# V2_7_7.net
KiCad netlist of a schematic drawn in EAGLE
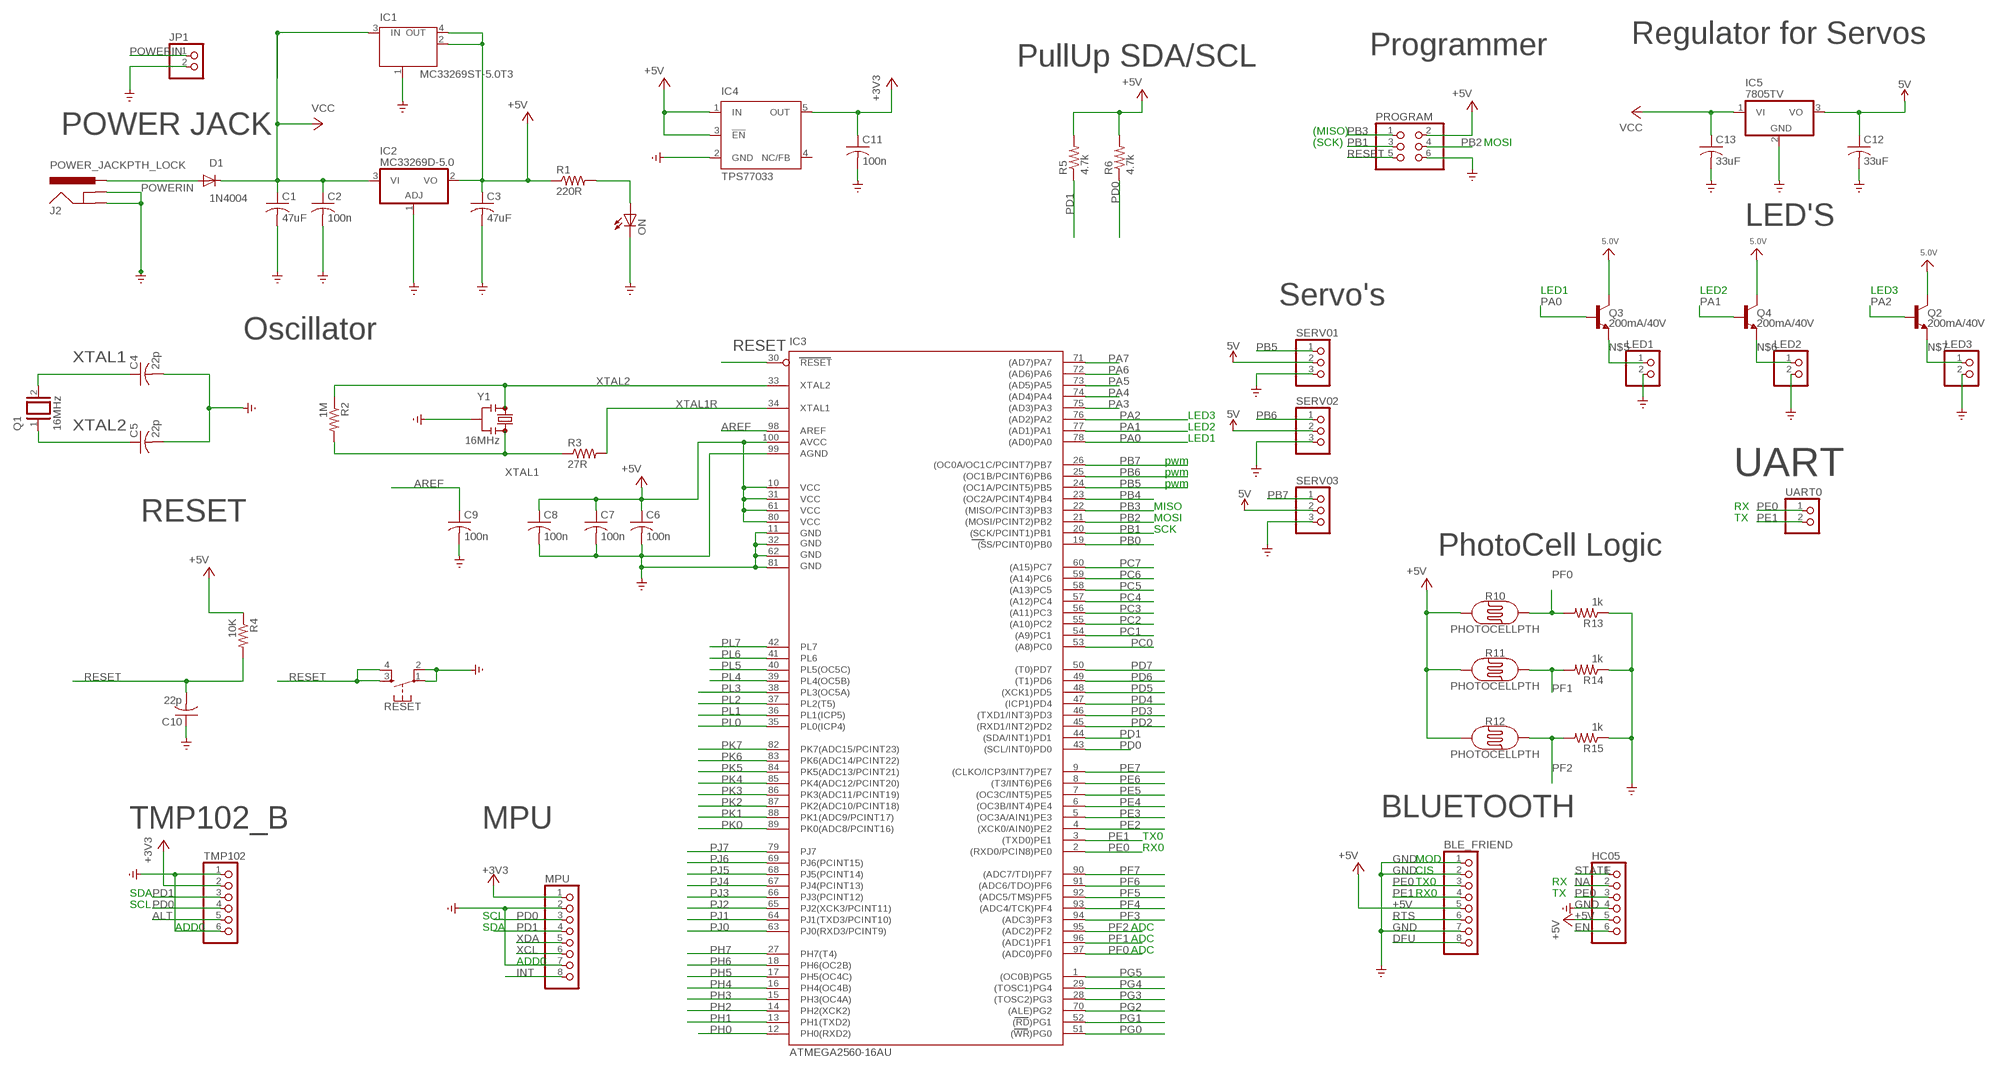
[diagram p0: schematic, sheet 1, part 1 of 2]
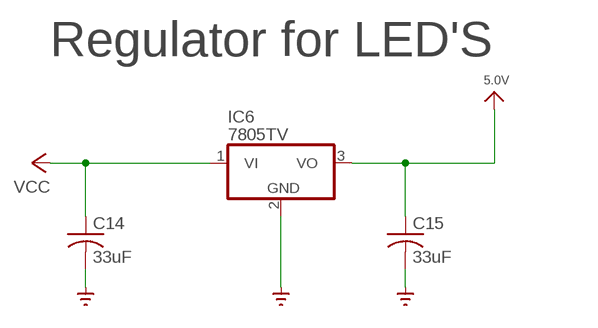
[diagram p1: schematic, sheet 1, part 2 of 2]

(export (version "E")
  (design (tool "Eeschema 10.0.6"))
  (components
    (comp (ref "BLE_FRIEND")
      (value "PINHD-1X8")
      (footprint "eagle-import:1X08")
      (libsource (lib "eagle-import") (part "PINHD-1X8"))
    )
    (comp (ref "C1")
      (value "47uF")
      (footprint "eagle-import:C025-024X044")
      (libsource (lib "eagle-import") (part "C-US025-024X044"))
    )
    (comp (ref "C2")
      (value "100n")
      (footprint "eagle-import:C025-024X044")
      (libsource (lib "eagle-import") (part "C-US025-024X044"))
    )
    (comp (ref "C3")
      (value "47uF")
      (footprint "eagle-import:C025-024X044")
      (libsource (lib "eagle-import") (part "C-US025-024X044"))
    )
    (comp (ref "C4")
      (value "22p")
      (footprint "eagle-import:C025-024X044")
      (libsource (lib "eagle-import") (part "C-US025-024X044"))
    )
    (comp (ref "C5")
      (value "22p")
      (footprint "eagle-import:C025-024X044")
      (libsource (lib "eagle-import") (part "C-US025-024X044"))
    )
    (comp (ref "C6")
      (value "100n")
      (footprint "eagle-import:C025-024X044")
      (libsource (lib "eagle-import") (part "C-US025-024X044"))
    )
    (comp (ref "C7")
      (value "100n")
      (footprint "eagle-import:C025-024X044")
      (libsource (lib "eagle-import") (part "C-US025-024X044"))
    )
    (comp (ref "C8")
      (value "100n")
      (footprint "eagle-import:C025-024X044")
      (libsource (lib "eagle-import") (part "C-US025-024X044"))
    )
    (comp (ref "C9")
      (value "100n")
      (footprint "eagle-import:C025-024X044")
      (libsource (lib "eagle-import") (part "C-US025-024X044"))
    )
    (comp (ref "C10")
      (value "22p")
      (footprint "eagle-import:C025-024X044")
      (libsource (lib "eagle-import") (part "C-US025-024X044"))
    )
    (comp (ref "C11")
      (value "100n")
      (footprint "eagle-import:C025-024X044")
      (libsource (lib "eagle-import") (part "C-US025-024X044"))
    )
    (comp (ref "C12")
      (value "33uF")
      (footprint "eagle-import:C025-024X044")
      (libsource (lib "eagle-import") (part "C-US025-024X044"))
    )
    (comp (ref "C13")
      (value "33uF")
      (footprint "eagle-import:C025-024X044")
      (libsource (lib "eagle-import") (part "C-US025-024X044"))
    )
    (comp (ref "C14")
      (value "33uF")
      (footprint "eagle-import:C025-024X044")
      (libsource (lib "eagle-import") (part "C-US025-024X044"))
    )
    (comp (ref "C15")
      (value "33uF")
      (footprint "eagle-import:C025-024X044")
      (libsource (lib "eagle-import") (part "C-US025-024X044"))
    )
    (comp (ref "D1")
      (value "1N4004")
      (footprint "eagle-import:DO41-10")
      (libsource (lib "eagle-import") (part "1N4004"))
    )
    (comp (ref "HC05")
      (value "PINHD-1X6")
      (footprint "eagle-import:1X06")
      (libsource (lib "eagle-import") (part "pinhead@1_PINHD-1X6"))
    )
    (comp (ref "IC1")
      (value "MC33269ST-5.0T3")
      (footprint "eagle-import:SOT223")
      (libsource (lib "eagle-import") (part "MC33269ST-3.3T3"))
    )
    (comp (ref "IC2")
      (value "MC33269D-5.0")
      (footprint "eagle-import:DPACK")
      (libsource (lib "eagle-import") (part "MC33269?D-5.0"))
    )
    (comp (ref "IC3")
      (value "ATMEGA2560-16AU")
      (footprint "eagle-import:TQFP100")
      (libsource (lib "eagle-import") (part "ATMEGAAU2560-16"))
    )
    (comp (ref "IC4")
      (value "TPS77033")
      (footprint "eagle-import:SOT23-DBV")
      (fields (field (name "MF") "TEXAS INSTRUMENTS") (field (name "MPN") "TPS77033DBVT"))
      (libsource (lib "eagle-import") (part "TPS77033"))
    )
    (comp (ref "IC5")
      (value "7805TV")
      (footprint "eagle-import:TO220V")
      (libsource (lib "eagle-import") (part "78TV05"))
    )
    (comp (ref "IC6")
      (value "7805TV")
      (footprint "eagle-import:TO220V")
      (libsource (lib "eagle-import") (part "78TV05"))
    )
    (comp (ref "J2")
      (value "POWER_JACKPTH_LOCK")
      (footprint "eagle-import:POWER_JACK_PTH_LOCK")
      (libsource (lib "eagle-import") (part "POWER_JACKPTH_LOCK"))
    )
    (comp (ref "JP1")
      (value "PINHD-1X2")
      (footprint "eagle-import:1X02")
      (libsource (lib "eagle-import") (part "pinhead@1_PINHD-1X2"))
    )
    (comp (ref "LED1")
      (value "PINHD-1X2")
      (footprint "eagle-import:1X02")
      (libsource (lib "eagle-import") (part "PINHD-1X2"))
    )
    (comp (ref "LED2")
      (value "PINHD-1X2")
      (footprint "eagle-import:1X02")
      (libsource (lib "eagle-import") (part "PINHD-1X2"))
    )
    (comp (ref "LED3")
      (value "PINHD-1X2")
      (footprint "eagle-import:1X02")
      (libsource (lib "eagle-import") (part "PINHD-1X2"))
    )
    (comp (ref "MPU")
      (value "PINHD-1X8")
      (footprint "eagle-import:1X08")
      (libsource (lib "eagle-import") (part "PINHD-1X8"))
    )
    (comp (ref "ON")
      (value "LED3MM")
      (footprint "eagle-import:LED3MM")
      (libsource (lib "eagle-import") (part "LED3MM"))
    )
    (comp (ref "PROGRAM")
      (value "PINHD-2X3")
      (footprint "eagle-import:2X03")
      (libsource (lib "eagle-import") (part "PINHD-2X3"))
    )
    (comp (ref "Q1")
      (value "16MHz")
      (footprint "eagle-import:QS")
      (libsource (lib "eagle-import") (part "XTAL/S"))
    )
    (comp (ref "Q2")
      (value "200mA/40V")
      (footprint "eagle-import:TO-92")
      (libsource (lib "eagle-import") (part "TRANS_NPN-2N3904"))
    )
    (comp (ref "Q3")
      (value "200mA/40V")
      (footprint "eagle-import:TO-92")
      (libsource (lib "eagle-import") (part "TRANS_NPN-2N3904"))
    )
    (comp (ref "Q4")
      (value "200mA/40V")
      (footprint "eagle-import:TO-92")
      (libsource (lib "eagle-import") (part "TRANS_NPN-2N3904"))
    )
    (comp (ref "R1")
      (value "220R")
      (footprint "eagle-import:0204V")
      (libsource (lib "eagle-import") (part "R-US_0204/2V"))
    )
    (comp (ref "R2")
      (value "1M")
      (footprint "eagle-import:0204V")
      (libsource (lib "eagle-import") (part "R-US_0204/2V"))
    )
    (comp (ref "R3")
      (value "27R")
      (footprint "eagle-import:0204V")
      (libsource (lib "eagle-import") (part "R-US_0204/2V"))
    )
    (comp (ref "R4")
      (value "10K")
      (footprint "eagle-import:0204V")
      (libsource (lib "eagle-import") (part "R-US_0204/2V"))
    )
    (comp (ref "R5")
      (value "4.7k")
      (footprint "eagle-import:0204V")
      (libsource (lib "eagle-import") (part "R-US_0204/2V"))
    )
    (comp (ref "R6")
      (value "4.7k")
      (footprint "eagle-import:0204V")
      (libsource (lib "eagle-import") (part "R-US_0204/2V"))
    )
    (comp (ref "R10")
      (value "PHOTOCELLPTH")
      (footprint "eagle-import:PHOTOCELL")
      (libsource (lib "eagle-import") (part "PHOTOCELLPTH"))
    )
    (comp (ref "R11")
      (value "PHOTOCELLPTH")
      (footprint "eagle-import:PHOTOCELL")
      (libsource (lib "eagle-import") (part "PHOTOCELLPTH"))
    )
    (comp (ref "R12")
      (value "PHOTOCELLPTH")
      (footprint "eagle-import:PHOTOCELL")
      (libsource (lib "eagle-import") (part "PHOTOCELLPTH"))
    )
    (comp (ref "R13")
      (value "1k")
      (footprint "eagle-import:0204V")
      (libsource (lib "eagle-import") (part "R-US_0204/2V"))
    )
    (comp (ref "R14")
      (value "1k")
      (footprint "eagle-import:0204V")
      (libsource (lib "eagle-import") (part "R-US_0204/2V"))
    )
    (comp (ref "R15")
      (value "1k")
      (footprint "eagle-import:0204V")
      (libsource (lib "eagle-import") (part "R-US_0204/2V"))
    )
    (comp (ref "RESET")
      (value "MOMENTARY-SWITCH-SPST-2-SMD-5.2MM")
      (footprint "eagle-import:TACTILE_SWITCH_SMD_5.2MM")
      (libsource (lib "eagle-import") (part "MOMENTARY-SWITCH-SPST-2-SMD-5.2MM"))
    )
    (comp (ref "SERV01")
      (value "PINHD-1X3")
      (footprint "eagle-import:1X03")
      (libsource (lib "eagle-import") (part "PINHD-1X3"))
    )
    (comp (ref "SERV02")
      (value "PINHD-1X3")
      (footprint "eagle-import:1X03")
      (libsource (lib "eagle-import") (part "PINHD-1X3"))
    )
    (comp (ref "SERV03")
      (value "PINHD-1X3")
      (footprint "eagle-import:1X03")
      (libsource (lib "eagle-import") (part "PINHD-1X3"))
    )
    (comp (ref "TMP102")
      (value "PINHD-1X6")
      (footprint "eagle-import:1X06")
      (libsource (lib "eagle-import") (part "PINHD-1X6"))
    )
    (comp (ref "UART0")
      (value "PINHD-1X2")
      (footprint "eagle-import:1X02")
      (libsource (lib "eagle-import") (part "PINHD-1X2"))
    )
    (comp (ref "Y1")
      (value "16MHz")
      (footprint "eagle-import:RESONATOR-SMD-3.2X1.3")
      (libsource (lib "eagle-import") (part "RESONATORSMD-3.2X1.3"))
    )
  )
  (nets
    (net (code "1") (name "+3V3") (class "Default")
      (node (ref "C11") (pin "1") (pinfunction "1_1") (pintype "passive"))
      (node (ref "IC4") (pin "5") (pinfunction "OUT_5") (pintype "passive"))
      (node (ref "MPU") (pin "1") (pinfunction "1_1") (pintype "passive"))
      (node (ref "TMP102") (pin "2") (pinfunction "2_2") (pintype "passive"))
    )
    (net (code "2") (name "+5V") (class "Default")
      (node (ref "BLE_FRIEND") (pin "5") (pinfunction "5_5") (pintype "passive"))
      (node (ref "C3") (pin "1") (pinfunction "1_1") (pintype "passive"))
      (node (ref "C6") (pin "1") (pinfunction "1_1") (pintype "passive"))
      (node (ref "C7") (pin "1") (pinfunction "1_1") (pintype "passive"))
      (node (ref "C8") (pin "1") (pinfunction "1_1") (pintype "passive"))
      (node (ref "HC05") (pin "5") (pinfunction "5_5") (pintype "passive"))
      (node (ref "IC1") (pin "2") (pinfunction "OUT_2") (pintype "passive"))
      (node (ref "IC1") (pin "4") (pinfunction "OUT_4") (pintype "passive"))
      (node (ref "IC2") (pin "2") (pinfunction "VO_2") (pintype "passive"))
      (node (ref "IC3") (pin "10") (pinfunction "VCC_10") (pintype "power_in"))
      (node (ref "IC3") (pin "100") (pinfunction "AVCC_100") (pintype "power_in"))
      (node (ref "IC3") (pin "31") (pinfunction "VCC1_31") (pintype "power_in"))
      (node (ref "IC3") (pin "61") (pinfunction "VCC2_61") (pintype "power_in"))
      (node (ref "IC3") (pin "80") (pinfunction "VCC3_80") (pintype "power_in"))
      (node (ref "IC4") (pin "1") (pinfunction "IN_1") (pintype "input"))
      (node (ref "IC4") (pin "3") (pinfunction "~{EN}_3") (pintype "input"))
      (node (ref "PROGRAM") (pin "2") (pinfunction "2_2") (pintype "passive"))
      (node (ref "R1") (pin "1") (pinfunction "1_1") (pintype "passive"))
      (node (ref "R10") (pin "1") (pinfunction "P$1_1") (pintype "bidirectional"))
      (node (ref "R11") (pin "1") (pinfunction "P$1_1") (pintype "bidirectional"))
      (node (ref "R12") (pin "1") (pinfunction "P$1_1") (pintype "bidirectional"))
      (node (ref "R4") (pin "1") (pinfunction "1_1") (pintype "passive"))
      (node (ref "R5") (pin "2") (pinfunction "2_2") (pintype "passive"))
      (node (ref "R6") (pin "2") (pinfunction "2_2") (pintype "passive"))
    )
    (net (code "3") (name "/ALT") (class "Default")
      (node (ref "TMP102") (pin "5") (pinfunction "5_5") (pintype "passive"))
    )
    (net (code "4") (name "/AREF") (class "Default")
      (node (ref "C9") (pin "1") (pinfunction "1_1") (pintype "passive"))
      (node (ref "IC3") (pin "98") (pinfunction "AREF_98") (pintype "bidirectional"))
    )
    (net (code "5") (name "/DFU") (class "Default")
      (node (ref "BLE_FRIEND") (pin "8") (pinfunction "8_8") (pintype "passive"))
    )
    (net (code "6") (name "/EN") (class "Default")
      (node (ref "HC05") (pin "6") (pinfunction "6_6") (pintype "passive"))
    )
    (net (code "7") (name "/INT") (class "Default")
      (node (ref "MPU") (pin "8") (pinfunction "8_8") (pintype "passive"))
    )
    (net (code "8") (name "/N$5") (class "Default")
      (node (ref "LED1") (pin "1") (pinfunction "1_1") (pintype "passive"))
      (node (ref "Q3") (pin "1") (pinfunction "E_1") (pintype "passive"))
    )
    (net (code "9") (name "/N$6") (class "Default")
      (node (ref "LED2") (pin "1") (pinfunction "1_1") (pintype "passive"))
      (node (ref "Q4") (pin "1") (pinfunction "E_1") (pintype "passive"))
    )
    (net (code "10") (name "/N$7") (class "Default")
      (node (ref "LED3") (pin "1") (pinfunction "1_1") (pintype "passive"))
      (node (ref "Q2") (pin "1") (pinfunction "E_1") (pintype "passive"))
    )
    (net (code "11") (name "/NA") (class "Default")
      (node (ref "HC05") (pin "2") (pinfunction "2_2") (pintype "passive"))
    )
    (net (code "12") (name "/PA0") (class "Default")
      (node (ref "IC3") (pin "78") (pinfunction "(AD0)PA0_78") (pintype "bidirectional"))
      (node (ref "Q3") (pin "2") (pinfunction "B_2") (pintype "passive"))
    )
    (net (code "13") (name "/PA1") (class "Default")
      (node (ref "IC3") (pin "77") (pinfunction "(AD1)PA1_77") (pintype "bidirectional"))
      (node (ref "Q4") (pin "2") (pinfunction "B_2") (pintype "passive"))
    )
    (net (code "14") (name "/PA2") (class "Default")
      (node (ref "IC3") (pin "76") (pinfunction "(AD2)PA2_76") (pintype "bidirectional"))
      (node (ref "Q2") (pin "2") (pinfunction "B_2") (pintype "passive"))
    )
    (net (code "15") (name "/PA3") (class "Default")
      (node (ref "IC3") (pin "75") (pinfunction "(AD3)PA3_75") (pintype "bidirectional"))
    )
    (net (code "16") (name "/PA4") (class "Default")
      (node (ref "IC3") (pin "74") (pinfunction "(AD4)PA4_74") (pintype "bidirectional"))
    )
    (net (code "17") (name "/PA5") (class "Default")
      (node (ref "IC3") (pin "73") (pinfunction "(AD5)PA5_73") (pintype "bidirectional"))
    )
    (net (code "18") (name "/PA6") (class "Default")
      (node (ref "IC3") (pin "72") (pinfunction "(AD6)PA6_72") (pintype "bidirectional"))
    )
    (net (code "19") (name "/PA7") (class "Default")
      (node (ref "IC3") (pin "71") (pinfunction "(AD7)PA7_71") (pintype "bidirectional"))
    )
    (net (code "20") (name "/PB0") (class "Default")
      (node (ref "IC3") (pin "19") (pinfunction "(SS/PCINT0)PB0_19") (pintype "bidirectional"))
    )
    (net (code "21") (name "/PB1") (class "Default")
      (node (ref "IC3") (pin "20") (pinfunction "(SCK/PCINT1)PB1_20") (pintype "bidirectional"))
      (node (ref "PROGRAM") (pin "3") (pinfunction "3_3") (pintype "passive"))
    )
    (net (code "22") (name "/PB2") (class "Default")
      (node (ref "IC3") (pin "21") (pinfunction "(MOSI/PCINT2)PB2_21") (pintype "bidirectional"))
      (node (ref "PROGRAM") (pin "4") (pinfunction "4_4") (pintype "passive"))
    )
    (net (code "23") (name "/PB3") (class "Default")
      (node (ref "IC3") (pin "22") (pinfunction "(MISO/PCINT3)PB3_22") (pintype "bidirectional"))
      (node (ref "PROGRAM") (pin "1") (pinfunction "1_1") (pintype "passive"))
    )
    (net (code "24") (name "/PB4") (class "Default")
      (node (ref "IC3") (pin "23") (pinfunction "(OC2A/PCINT4)PB4_23") (pintype "bidirectional"))
    )
    (net (code "25") (name "/PB5") (class "Default")
      (node (ref "IC3") (pin "24") (pinfunction "(OC1A/PCINT5)PB5_24") (pintype "bidirectional"))
      (node (ref "SERV01") (pin "1") (pinfunction "1_1") (pintype "passive"))
    )
    (net (code "26") (name "/PB6") (class "Default")
      (node (ref "IC3") (pin "25") (pinfunction "(OC1B/PCINT6)PB6_25") (pintype "bidirectional"))
      (node (ref "SERV02") (pin "1") (pinfunction "1_1") (pintype "passive"))
    )
    (net (code "27") (name "/PB7") (class "Default")
      (node (ref "IC3") (pin "26") (pinfunction "(OC0A/OC1C/PCINT7)PB7_26") (pintype "bidirectional"))
      (node (ref "SERV03") (pin "1") (pinfunction "1_1") (pintype "passive"))
    )
    (net (code "28") (name "/PC0") (class "Default")
      (node (ref "IC3") (pin "53") (pinfunction "(A8)PC0_53") (pintype "bidirectional"))
    )
    (net (code "29") (name "/PC1") (class "Default")
      (node (ref "IC3") (pin "54") (pinfunction "(A9)PC1_54") (pintype "bidirectional"))
    )
    (net (code "30") (name "/PC2") (class "Default")
      (node (ref "IC3") (pin "55") (pinfunction "(A10)PC2_55") (pintype "bidirectional"))
    )
    (net (code "31") (name "/PC3") (class "Default")
      (node (ref "IC3") (pin "56") (pinfunction "(A11)PC3_56") (pintype "bidirectional"))
    )
    (net (code "32") (name "/PC4") (class "Default")
      (node (ref "IC3") (pin "57") (pinfunction "(A12)PC4_57") (pintype "bidirectional"))
    )
    (net (code "33") (name "/PC5") (class "Default")
      (node (ref "IC3") (pin "58") (pinfunction "(A13)PC5_58") (pintype "bidirectional"))
    )
    (net (code "34") (name "/PC6") (class "Default")
      (node (ref "IC3") (pin "59") (pinfunction "(A14)PC6_59") (pintype "bidirectional"))
    )
    (net (code "35") (name "/PC7") (class "Default")
      (node (ref "IC3") (pin "60") (pinfunction "(A15)PC7_60") (pintype "bidirectional"))
    )
    (net (code "36") (name "/PD0") (class "Default")
      (node (ref "IC3") (pin "43") (pinfunction "(SCL/INT0)PD0_43") (pintype "bidirectional"))
      (node (ref "MPU") (pin "3") (pinfunction "3_3") (pintype "passive"))
      (node (ref "R6") (pin "1") (pinfunction "1_1") (pintype "passive"))
      (node (ref "TMP102") (pin "4") (pinfunction "4_4") (pintype "passive"))
    )
    (net (code "37") (name "/PD1") (class "Default")
      (node (ref "IC3") (pin "44") (pinfunction "(SDA/INT1)PD1_44") (pintype "bidirectional"))
      (node (ref "MPU") (pin "4") (pinfunction "4_4") (pintype "passive"))
      (node (ref "R5") (pin "1") (pinfunction "1_1") (pintype "passive"))
      (node (ref "TMP102") (pin "3") (pinfunction "3_3") (pintype "passive"))
    )
    (net (code "38") (name "/PD2") (class "Default")
      (node (ref "IC3") (pin "45") (pinfunction "(RXD1/INT2)PD2_45") (pintype "bidirectional"))
    )
    (net (code "39") (name "/PD3") (class "Default")
      (node (ref "IC3") (pin "46") (pinfunction "(TXD1/INT3)PD3_46") (pintype "bidirectional"))
    )
    (net (code "40") (name "/PD4") (class "Default")
      (node (ref "IC3") (pin "47") (pinfunction "(ICP1)PD4_47") (pintype "bidirectional"))
    )
    (net (code "41") (name "/PD5") (class "Default")
      (node (ref "IC3") (pin "48") (pinfunction "(XCK1)PD5_48") (pintype "bidirectional"))
    )
    (net (code "42") (name "/PD6") (class "Default")
      (node (ref "IC3") (pin "49") (pinfunction "(T1)PD6_49") (pintype "bidirectional"))
    )
    (net (code "43") (name "/PD7") (class "Default")
      (node (ref "IC3") (pin "50") (pinfunction "(T0)PD7_50") (pintype "bidirectional"))
    )
    (net (code "44") (name "/PE0") (class "Default")
      (node (ref "BLE_FRIEND") (pin "3") (pinfunction "3_3") (pintype "passive"))
      (node (ref "HC05") (pin "3") (pinfunction "3_3") (pintype "passive"))
      (node (ref "IC3") (pin "2") (pinfunction "(RXD0/PCIN8)PE0_2") (pintype "bidirectional"))
      (node (ref "UART0") (pin "1") (pinfunction "1_1") (pintype "passive"))
    )
    (net (code "45") (name "/PE1") (class "Default")
      (node (ref "BLE_FRIEND") (pin "4") (pinfunction "4_4") (pintype "passive"))
      (node (ref "IC3") (pin "3") (pinfunction "(TXD0)PE1_3") (pintype "bidirectional"))
      (node (ref "UART0") (pin "2") (pinfunction "2_2") (pintype "passive"))
    )
    (net (code "46") (name "/PE2") (class "Default")
      (node (ref "IC3") (pin "4") (pinfunction "(XCK0/AIN0)PE2_4") (pintype "bidirectional"))
    )
    (net (code "47") (name "/PE3") (class "Default")
      (node (ref "IC3") (pin "5") (pinfunction "(OC3A/AIN1)PE3_5") (pintype "bidirectional"))
    )
    (net (code "48") (name "/PE4") (class "Default")
      (node (ref "IC3") (pin "6") (pinfunction "(OC3B/INT4)PE4_6") (pintype "bidirectional"))
    )
    (net (code "49") (name "/PE5") (class "Default")
      (node (ref "IC3") (pin "7") (pinfunction "(OC3C/INT5)PE5_7") (pintype "bidirectional"))
    )
    (net (code "50") (name "/PE6") (class "Default")
      (node (ref "IC3") (pin "8") (pinfunction "(T3/INT6)PE6_8") (pintype "bidirectional"))
    )
    (net (code "51") (name "/PE7") (class "Default")
      (node (ref "IC3") (pin "9") (pinfunction "(CLKO/ICP3/INT7)PE7_9") (pintype "bidirectional"))
    )
    (net (code "52") (name "/PF0") (class "Default")
      (node (ref "IC3") (pin "97") (pinfunction "(ADC0)PF0_97") (pintype "bidirectional"))
      (node (ref "R10") (pin "2") (pinfunction "P$2_2") (pintype "bidirectional"))
      (node (ref "R13") (pin "2") (pinfunction "2_2") (pintype "passive"))
    )
    (net (code "53") (name "/PF1") (class "Default")
      (node (ref "IC3") (pin "96") (pinfunction "(ADC1)PF1_96") (pintype "bidirectional"))
      (node (ref "R11") (pin "2") (pinfunction "P$2_2") (pintype "bidirectional"))
      (node (ref "R14") (pin "2") (pinfunction "2_2") (pintype "passive"))
    )
    (net (code "54") (name "/PF2") (class "Default")
      (node (ref "IC3") (pin "95") (pinfunction "(ADC2)PF2_95") (pintype "bidirectional"))
      (node (ref "R12") (pin "2") (pinfunction "P$2_2") (pintype "bidirectional"))
      (node (ref "R15") (pin "2") (pinfunction "2_2") (pintype "passive"))
    )
    (net (code "55") (name "/PF3") (class "Default")
      (node (ref "IC3") (pin "94") (pinfunction "(ADC3)PF3_94") (pintype "bidirectional"))
    )
    (net (code "56") (name "/PF4") (class "Default")
      (node (ref "IC3") (pin "93") (pinfunction "(ADC4/TCK)PF4_93") (pintype "bidirectional"))
    )
    (net (code "57") (name "/PF5") (class "Default")
      (node (ref "IC3") (pin "92") (pinfunction "(ADC5/TMS)PF5_92") (pintype "bidirectional"))
    )
    (net (code "58") (name "/PF6") (class "Default")
      (node (ref "IC3") (pin "91") (pinfunction "(ADC6/TDO)PF6_91") (pintype "bidirectional"))
    )
    (net (code "59") (name "/PF7") (class "Default")
      (node (ref "IC3") (pin "90") (pinfunction "(ADC7/TDI)PF7_90") (pintype "bidirectional"))
    )
    (net (code "60") (name "/PG0") (class "Default")
      (node (ref "IC3") (pin "51") (pinfunction "(WR)PG0_51") (pintype "bidirectional"))
    )
    (net (code "61") (name "/PG1") (class "Default")
      (node (ref "IC3") (pin "52") (pinfunction "(RD)PG1_52") (pintype "bidirectional"))
    )
    (net (code "62") (name "/PG2") (class "Default")
      (node (ref "IC3") (pin "70") (pinfunction "(ALE)PG2_70") (pintype "bidirectional"))
    )
    (net (code "63") (name "/PG3") (class "Default")
      (node (ref "IC3") (pin "28") (pinfunction "(TOSC2)PG3_28") (pintype "bidirectional"))
    )
    (net (code "64") (name "/PG4") (class "Default")
      (node (ref "IC3") (pin "29") (pinfunction "(TOSC1)PG4_29") (pintype "bidirectional"))
    )
    (net (code "65") (name "/PG5") (class "Default")
      (node (ref "IC3") (pin "1") (pinfunction "(OC0B)PG5_1") (pintype "bidirectional"))
    )
    (net (code "66") (name "/PH0") (class "Default")
      (node (ref "IC3") (pin "12") (pinfunction "PH0(RXD2)_12") (pintype "bidirectional"))
    )
    (net (code "67") (name "/PH1") (class "Default")
      (node (ref "IC3") (pin "13") (pinfunction "PH1(TXD2)_13") (pintype "bidirectional"))
    )
    (net (code "68") (name "/PH2") (class "Default")
      (node (ref "IC3") (pin "14") (pinfunction "PH2(XCK2)_14") (pintype "bidirectional"))
    )
    (net (code "69") (name "/PH3") (class "Default")
      (node (ref "IC3") (pin "15") (pinfunction "PH3(OC4A)_15") (pintype "bidirectional"))
    )
    (net (code "70") (name "/PH4") (class "Default")
      (node (ref "IC3") (pin "16") (pinfunction "PH4(OC4B)_16") (pintype "bidirectional"))
    )
    (net (code "71") (name "/PH5") (class "Default")
      (node (ref "IC3") (pin "17") (pinfunction "PH5(OC4C)_17") (pintype "bidirectional"))
    )
    (net (code "72") (name "/PH6") (class "Default")
      (node (ref "IC3") (pin "18") (pinfunction "PH6(OC2B)_18") (pintype "bidirectional"))
    )
    (net (code "73") (name "/PH7") (class "Default")
      (node (ref "IC3") (pin "27") (pinfunction "PH7(T4)_27") (pintype "bidirectional"))
    )
    (net (code "74") (name "/PJ0") (class "Default")
      (node (ref "IC3") (pin "63") (pinfunction "PJ0(RXD3/PCINT9)_63") (pintype "bidirectional"))
    )
    (net (code "75") (name "/PJ1") (class "Default")
      (node (ref "IC3") (pin "64") (pinfunction "PJ1(TXD3/PCINT10)_64") (pintype "bidirectional"))
    )
    (net (code "76") (name "/PJ2") (class "Default")
      (node (ref "IC3") (pin "65") (pinfunction "PJ2(XCK3/PCINT11)_65") (pintype "bidirectional"))
    )
    (net (code "77") (name "/PJ3") (class "Default")
      (node (ref "IC3") (pin "66") (pinfunction "PJ3(PCINT12)_66") (pintype "bidirectional"))
    )
    (net (code "78") (name "/PJ4") (class "Default")
      (node (ref "IC3") (pin "67") (pinfunction "PJ4(PCINT13)_67") (pintype "bidirectional"))
    )
    (net (code "79") (name "/PJ5") (class "Default")
      (node (ref "IC3") (pin "68") (pinfunction "PJ5(PCINT14)_68") (pintype "bidirectional"))
    )
    (net (code "80") (name "/PJ6") (class "Default")
      (node (ref "IC3") (pin "69") (pinfunction "PJ6(PCINT15)_69") (pintype "bidirectional"))
    )
    (net (code "81") (name "/PJ7") (class "Default")
      (node (ref "IC3") (pin "79") (pinfunction "PJ7_79") (pintype "bidirectional"))
    )
    (net (code "82") (name "/PK0") (class "Default")
      (node (ref "IC3") (pin "89") (pinfunction "PK0(ADC8/PCINT16)_89") (pintype "bidirectional"))
    )
    (net (code "83") (name "/PK1") (class "Default")
      (node (ref "IC3") (pin "88") (pinfunction "PK1(ADC9/PCINT17)_88") (pintype "bidirectional"))
    )
    (net (code "84") (name "/PK2") (class "Default")
      (node (ref "IC3") (pin "87") (pinfunction "PK2(ADC10/PCINT18)_87") (pintype "bidirectional"))
    )
    (net (code "85") (name "/PK3") (class "Default")
      (node (ref "IC3") (pin "86") (pinfunction "PK3(ADC11/PCINT19)_86") (pintype "bidirectional"))
    )
    (net (code "86") (name "/PK4") (class "Default")
      (node (ref "IC3") (pin "85") (pinfunction "PK4(ADC12/PCINT20)_85") (pintype "bidirectional"))
    )
    (net (code "87") (name "/PK5") (class "Default")
      (node (ref "IC3") (pin "84") (pinfunction "PK5(ADC13/PCINT21)_84") (pintype "bidirectional"))
    )
    (net (code "88") (name "/PK6") (class "Default")
      (node (ref "IC3") (pin "83") (pinfunction "PK6(ADC14/PCINT22)_83") (pintype "bidirectional"))
    )
    (net (code "89") (name "/PK7") (class "Default")
      (node (ref "IC3") (pin "82") (pinfunction "PK7(ADC15/PCINT23)_82") (pintype "bidirectional"))
    )
    (net (code "90") (name "/PL0") (class "Default")
      (node (ref "IC3") (pin "35") (pinfunction "PL0(ICP4)_35") (pintype "bidirectional"))
    )
    (net (code "91") (name "/PL1") (class "Default")
      (node (ref "IC3") (pin "36") (pinfunction "PL1(ICP5)_36") (pintype "bidirectional"))
    )
    (net (code "92") (name "/PL2") (class "Default")
      (node (ref "IC3") (pin "37") (pinfunction "PL2(T5)_37") (pintype "bidirectional"))
    )
    (net (code "93") (name "/PL3") (class "Default")
      (node (ref "IC3") (pin "38") (pinfunction "PL3(OC5A)_38") (pintype "bidirectional"))
    )
    (net (code "94") (name "/PL4") (class "Default")
      (node (ref "IC3") (pin "39") (pinfunction "PL4(OC5B)_39") (pintype "bidirectional"))
    )
    (net (code "95") (name "/PL5") (class "Default")
      (node (ref "IC3") (pin "40") (pinfunction "PL5(OC5C)_40") (pintype "bidirectional"))
    )
    (net (code "96") (name "/PL6") (class "Default")
      (node (ref "IC3") (pin "41") (pinfunction "PL6_41") (pintype "bidirectional"))
    )
    (net (code "97") (name "/PL7") (class "Default")
      (node (ref "IC3") (pin "42") (pinfunction "PL7_42") (pintype "bidirectional"))
    )
    (net (code "98") (name "/POWERIN") (class "Default")
      (node (ref "D1") (pin "A") (pinfunction "A_A") (pintype "passive"))
      (node (ref "J2") (pin "PWR") (pinfunction "PWR_PWR") (pintype "bidirectional"))
      (node (ref "JP1") (pin "1") (pinfunction "1_1") (pintype "passive"))
    )
    (net (code "99") (name "/RESET") (class "Default")
      (node (ref "C10") (pin "2") (pinfunction "2_2") (pintype "passive"))
      (node (ref "IC3") (pin "30") (pinfunction "RESET_30") (pintype "input"))
      (node (ref "PROGRAM") (pin "5") (pinfunction "5_5") (pintype "passive"))
      (node (ref "R4") (pin "2") (pinfunction "2_2") (pintype "passive"))
      (node (ref "RESET") (pin "3") (pinfunction "3_3") (pintype "passive"))
      (node (ref "RESET") (pin "4") (pinfunction "4_4") (pintype "passive"))
    )
    (net (code "100") (name "/RTS") (class "Default")
      (node (ref "BLE_FRIEND") (pin "6") (pinfunction "6_6") (pintype "passive"))
    )
    (net (code "101") (name "/STATE") (class "Default")
      (node (ref "HC05") (pin "1") (pinfunction "1_1") (pintype "passive"))
    )
    (net (code "102") (name "/XCL") (class "Default")
      (node (ref "MPU") (pin "6") (pinfunction "6_6") (pintype "passive"))
    )
    (net (code "103") (name "/XDA") (class "Default")
      (node (ref "MPU") (pin "5") (pinfunction "5_5") (pintype "passive"))
    )
    (net (code "104") (name "/XTAL1") (class "Default")
      (node (ref "C4") (pin "1") (pinfunction "1_1") (pintype "passive"))
      (node (ref "Q1") (pin "2") (pinfunction "2_2") (pintype "passive"))
      (node (ref "R2") (pin "2") (pinfunction "2_2") (pintype "passive"))
      (node (ref "R3") (pin "1") (pinfunction "1_1") (pintype "passive"))
      (node (ref "Y1") (pin "3") (pinfunction "3_3") (pintype "passive"))
    )
    (net (code "105") (name "/XTAL1R") (class "Default")
      (node (ref "IC3") (pin "34") (pinfunction "XTAL1_34") (pintype "input"))
      (node (ref "R3") (pin "2") (pinfunction "2_2") (pintype "passive"))
    )
    (net (code "106") (name "/XTAL2") (class "Default")
      (node (ref "C5") (pin "1") (pinfunction "1_1") (pintype "passive"))
      (node (ref "IC3") (pin "33") (pinfunction "XTAL2_33") (pintype "output"))
      (node (ref "Q1") (pin "1") (pinfunction "1_1") (pintype "passive"))
      (node (ref "R2") (pin "1") (pinfunction "1_1") (pintype "passive"))
      (node (ref "Y1") (pin "1") (pinfunction "1_1") (pintype "passive"))
    )
    (net (code "107") (name "5.0V") (class "Default")
      (node (ref "C15") (pin "1") (pinfunction "1_1") (pintype "passive"))
      (node (ref "IC6") (pin "3") (pinfunction "VO_3") (pintype "passive"))
      (node (ref "Q2") (pin "3") (pinfunction "C_3") (pintype "passive"))
      (node (ref "Q3") (pin "3") (pinfunction "C_3") (pintype "passive"))
      (node (ref "Q4") (pin "3") (pinfunction "C_3") (pintype "passive"))
    )
    (net (code "108") (name "5V") (class "Default")
      (node (ref "C12") (pin "1") (pinfunction "1_1") (pintype "passive"))
      (node (ref "IC5") (pin "3") (pinfunction "VO_3") (pintype "passive"))
      (node (ref "SERV01") (pin "2") (pinfunction "2_2") (pintype "passive"))
      (node (ref "SERV02") (pin "2") (pinfunction "2_2") (pintype "passive"))
      (node (ref "SERV03") (pin "2") (pinfunction "2_2") (pintype "passive"))
    )
    (net (code "109") (name "GND_") (class "Default")
      (node (ref "BLE_FRIEND") (pin "1") (pinfunction "1_1") (pintype "passive"))
      (node (ref "BLE_FRIEND") (pin "2") (pinfunction "2_2") (pintype "passive"))
      (node (ref "BLE_FRIEND") (pin "7") (pinfunction "7_7") (pintype "passive"))
      (node (ref "C1") (pin "2") (pinfunction "2_2") (pintype "passive"))
      (node (ref "C10") (pin "1") (pinfunction "1_1") (pintype "passive"))
      (node (ref "C11") (pin "2") (pinfunction "2_2") (pintype "passive"))
      (node (ref "C12") (pin "2") (pinfunction "2_2") (pintype "passive"))
      (node (ref "C13") (pin "2") (pinfunction "2_2") (pintype "passive"))
      (node (ref "C14") (pin "2") (pinfunction "2_2") (pintype "passive"))
      (node (ref "C15") (pin "2") (pinfunction "2_2") (pintype "passive"))
      (node (ref "C2") (pin "2") (pinfunction "2_2") (pintype "passive"))
      (node (ref "C3") (pin "2") (pinfunction "2_2") (pintype "passive"))
      (node (ref "C4") (pin "2") (pinfunction "2_2") (pintype "passive"))
      (node (ref "C5") (pin "2") (pinfunction "2_2") (pintype "passive"))
      (node (ref "C6") (pin "2") (pinfunction "2_2") (pintype "passive"))
      (node (ref "C7") (pin "2") (pinfunction "2_2") (pintype "passive"))
      (node (ref "C8") (pin "2") (pinfunction "2_2") (pintype "passive"))
      (node (ref "C9") (pin "2") (pinfunction "2_2") (pintype "passive"))
      (node (ref "HC05") (pin "4") (pinfunction "4_4") (pintype "passive"))
      (node (ref "IC1") (pin "1") (pinfunction "GND/ADJ_1") (pintype "input"))
      (node (ref "IC2") (pin "1") (pinfunction "ADJ_1") (pintype "input"))
      (node (ref "IC3") (pin "11") (pinfunction "GND_11") (pintype "power_in"))
      (node (ref "IC3") (pin "32") (pinfunction "GND1_32") (pintype "power_in"))
      (node (ref "IC3") (pin "62") (pinfunction "GND2_62") (pintype "power_in"))
      (node (ref "IC3") (pin "81") (pinfunction "GND3_81") (pintype "power_in"))
      (node (ref "IC3") (pin "99") (pinfunction "AGND_99") (pintype "power_in"))
      (node (ref "IC4") (pin "2") (pinfunction "GND_2") (pintype "power_in"))
      (node (ref "IC5") (pin "2") (pinfunction "GND_2") (pintype "passive"))
      (node (ref "IC6") (pin "2") (pinfunction "GND_2") (pintype "passive"))
      (node (ref "J2") (pin "GND") (pinfunction "GND_GND") (pintype "bidirectional"))
      (node (ref "J2") (pin "GNDBREAK") (pinfunction "GNDBREAK_GNDBREAK") (pintype "bidirectional"))
      (node (ref "JP1") (pin "2") (pinfunction "2_2") (pintype "passive"))
      (node (ref "LED1") (pin "2") (pinfunction "2_2") (pintype "passive"))
      (node (ref "LED2") (pin "2") (pinfunction "2_2") (pintype "passive"))
      (node (ref "LED3") (pin "2") (pinfunction "2_2") (pintype "passive"))
      (node (ref "MPU") (pin "2") (pinfunction "2_2") (pintype "passive"))
      (node (ref "MPU") (pin "7") (pinfunction "7_7") (pintype "passive"))
      (node (ref "ON") (pin "K") (pinfunction "C_K") (pintype "passive"))
      (node (ref "PROGRAM") (pin "6") (pinfunction "6_6") (pintype "passive"))
      (node (ref "R13") (pin "1") (pinfunction "1_1") (pintype "passive"))
      (node (ref "R14") (pin "1") (pinfunction "1_1") (pintype "passive"))
      (node (ref "R15") (pin "1") (pinfunction "1_1") (pintype "passive"))
      (node (ref "RESET") (pin "1") (pinfunction "1_1") (pintype "passive"))
      (node (ref "RESET") (pin "2") (pinfunction "2_2") (pintype "passive"))
      (node (ref "SERV01") (pin "3") (pinfunction "3_3") (pintype "passive"))
      (node (ref "SERV02") (pin "3") (pinfunction "3_3") (pintype "passive"))
      (node (ref "SERV03") (pin "3") (pinfunction "3_3") (pintype "passive"))
      (node (ref "TMP102") (pin "1") (pinfunction "1_1") (pintype "passive"))
      (node (ref "TMP102") (pin "6") (pinfunction "6_6") (pintype "passive"))
      (node (ref "Y1") (pin "2") (pinfunction "2_2") (pintype "passive"))
    )
    (net (code "110") (name "Net-(ON-PadA)") (class "Default")
      (node (ref "ON") (pin "A") (pinfunction "A_A") (pintype "passive"))
      (node (ref "R1") (pin "2") (pinfunction "2_2") (pintype "passive"))
    )
    (net (code "111") (name "VCC") (class "Default")
      (node (ref "C1") (pin "1") (pinfunction "1_1") (pintype "passive"))
      (node (ref "C13") (pin "1") (pinfunction "1_1") (pintype "passive"))
      (node (ref "C14") (pin "1") (pinfunction "1_1") (pintype "passive"))
      (node (ref "C2") (pin "1") (pinfunction "1_1") (pintype "passive"))
      (node (ref "D1") (pin "C") (pinfunction "C_C") (pintype "passive"))
      (node (ref "IC1") (pin "3") (pinfunction "IN_3") (pintype "input"))
      (node (ref "IC2") (pin "3") (pinfunction "VI_3") (pintype "input"))
      (node (ref "IC5") (pin "1") (pinfunction "VI_1") (pintype "input"))
      (node (ref "IC6") (pin "1") (pinfunction "VI_1") (pintype "input"))
    )
    (net (code "112") (name "unconnected-(IC4-NC{slash}FB-Pad4)") (class "Default")
      (node (ref "IC4") (pin "4") (pinfunction "NC/FB_4") (pintype "passive"))
    )
  )
)
